# Steuerplatine_V2_0.net
KiCad netlist of a schematic drawn in EAGLE
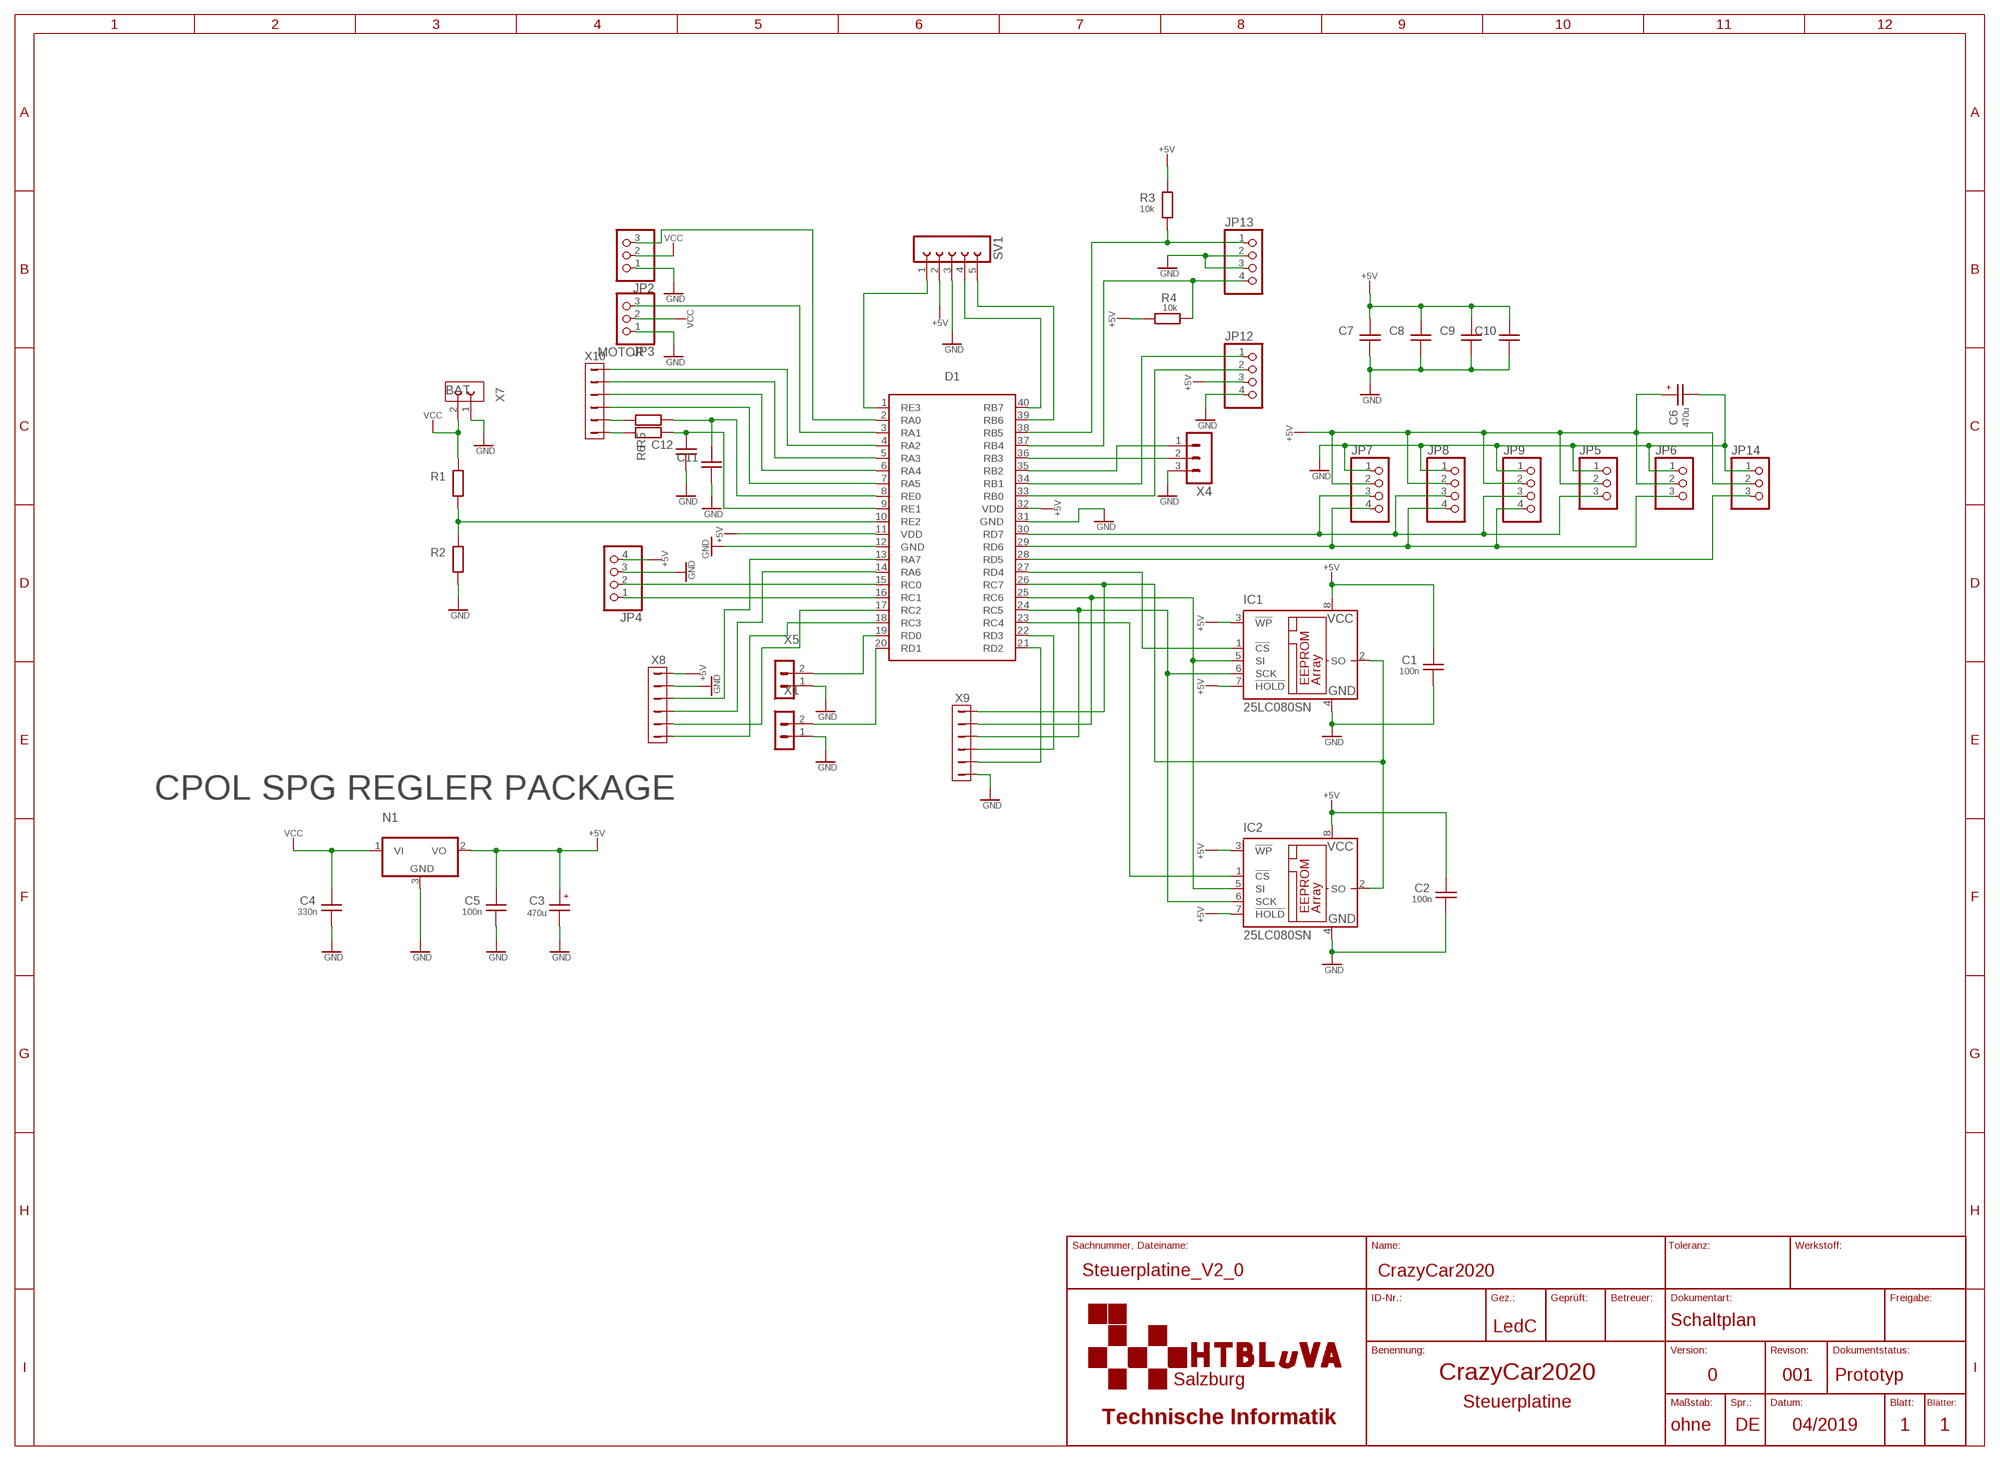
[diagram p0: schematic, sheet 1]

(export (version "E")
  (design (tool "Eeschema 10.0.6"))
  (components
    (comp (ref "C1")
      (value "100n")
      (footprint "eagle-import:C0603")
      (libsource (lib "eagle-import") (part "C-V_C0603"))
    )
    (comp (ref "C2")
      (value "100n")
      (footprint "eagle-import:C0603")
      (libsource (lib "eagle-import") (part "C-V_C0603"))
    )
    (comp (ref "C3")
      (value "470u")
      (footprint "eagle-import:E5-10,5")
      (libsource (lib "eagle-import") (part "C-POL-V_E5-10.5"))
    )
    (comp (ref "C4")
      (value "330n")
      (footprint "eagle-import:C1206")
      (libsource (lib "eagle-import") (part "C-V_C1206"))
    )
    (comp (ref "C5")
      (value "100n")
      (footprint "eagle-import:C1206")
      (libsource (lib "eagle-import") (part "C-V_C1206"))
    )
    (comp (ref "C6")
      (value "470u")
      (footprint "eagle-import:E5-10,5")
      (libsource (lib "eagle-import") (part "C-POL-V_E5-10.5"))
    )
    (comp (ref "C7")
      (value "C-V_C1206")
      (footprint "eagle-import:C1206")
      (libsource (lib "eagle-import") (part "C-V_C1206"))
    )
    (comp (ref "C8")
      (value "C-V_C1206")
      (footprint "eagle-import:C1206")
      (libsource (lib "eagle-import") (part "C-V_C1206"))
    )
    (comp (ref "C9")
      (value "C-V_C1206")
      (footprint "eagle-import:C1206")
      (libsource (lib "eagle-import") (part "C-V_C1206"))
    )
    (comp (ref "C10")
      (value "C-V_C1206")
      (footprint "eagle-import:C1206")
      (libsource (lib "eagle-import") (part "C-V_C1206"))
    )
    (comp (ref "C11")
      (value "C-V_C1206")
      (footprint "eagle-import:C1206")
      (libsource (lib "eagle-import") (part "C-V_C1206"))
    )
    (comp (ref "C12")
      (value "C-V_C1206")
      (footprint "eagle-import:C1206")
      (libsource (lib "eagle-import") (part "C-V_C1206"))
    )
    (comp (ref "D1")
      (value "EVAL_BRD_PIC18F46K421")
      (footprint "eagle-import:EVAL_BRD_PIC18F46K42")
      (libsource (lib "eagle-import") (part "EVAL_BRD_PIC18F46K421"))
    )
    (comp (ref "IC1")
      (value "25LC080SN")
      (footprint "eagle-import:SO-08")
      (fields (field (name "MF") "MICROCHIP") (field (name "MPN") "25LC080/SN"))
      (libsource (lib "eagle-import") (part "25SNLC080"))
    )
    (comp (ref "IC2")
      (value "25LC080SN")
      (footprint "eagle-import:SO-08")
      (fields (field (name "MF") "MICROCHIP") (field (name "MPN") "25LC080/SN"))
      (libsource (lib "eagle-import") (part "25SNLC080"))
    )
    (comp (ref "JP2")
      (value "PINHD-1X3")
      (footprint "eagle-import:1X03")
      (libsource (lib "eagle-import") (part "PINHD-1X3"))
    )
    (comp (ref "JP3")
      (value "PINHD-1X3")
      (footprint "eagle-import:1X03")
      (libsource (lib "eagle-import") (part "PINHD-1X3"))
    )
    (comp (ref "JP4")
      (value "PINHD-1X4")
      (footprint "eagle-import:1X04")
      (libsource (lib "eagle-import") (part "PINHD-1X4"))
    )
    (comp (ref "JP5")
      (value "PINHD-1X3")
      (footprint "eagle-import:1X03")
      (libsource (lib "eagle-import") (part "PINHD-1X3"))
    )
    (comp (ref "JP6")
      (value "PINHD-1X3")
      (footprint "eagle-import:1X03")
      (libsource (lib "eagle-import") (part "PINHD-1X3"))
    )
    (comp (ref "JP7")
      (value "PINHD-1X4")
      (footprint "eagle-import:1X04")
      (libsource (lib "eagle-import") (part "PINHD-1X4"))
    )
    (comp (ref "JP8")
      (value "PINHD-1X4")
      (footprint "eagle-import:1X04")
      (libsource (lib "eagle-import") (part "PINHD-1X4"))
    )
    (comp (ref "JP9")
      (value "PINHD-1X4")
      (footprint "eagle-import:1X04")
      (libsource (lib "eagle-import") (part "PINHD-1X4"))
    )
    (comp (ref "JP12")
      (value "PINHD-1X4")
      (footprint "eagle-import:1X04")
      (libsource (lib "eagle-import") (part "PINHD-1X4"))
    )
    (comp (ref "JP13")
      (value "PINHD-1X4")
      (footprint "eagle-import:1X04")
      (libsource (lib "eagle-import") (part "PINHD-1X4"))
    )
    (comp (ref "JP14")
      (value "PINHD-1X3")
      (footprint "eagle-import:1X03")
      (libsource (lib "eagle-import") (part "PINHD-1X3"))
    )
    (comp (ref "N1")
      (value "7805DT")
      (footprint "eagle-import:TO252")
      (libsource (lib "eagle-import") (part "78DT05"))
    )
    (comp (ref "R1")
      (value "R-V_R1206")
      (footprint "eagle-import:R1206")
      (libsource (lib "eagle-import") (part "R-V_R1206"))
    )
    (comp (ref "R2")
      (value "R-V_R1206")
      (footprint "eagle-import:R1206")
      (libsource (lib "eagle-import") (part "R-V_R1206"))
    )
    (comp (ref "R3")
      (value "10k")
      (footprint "eagle-import:R1206")
      (libsource (lib "eagle-import") (part "R-V_R1206"))
    )
    (comp (ref "R4")
      (value "10k")
      (footprint "eagle-import:R1206")
      (libsource (lib "eagle-import") (part "R-V_R1206"))
    )
    (comp (ref "R5")
      (value "R-V_R1206")
      (footprint "eagle-import:R1206")
      (libsource (lib "eagle-import") (part "R-V_R1206"))
    )
    (comp (ref "R6")
      (value "R-V_R1206")
      (footprint "eagle-import:R1206")
      (libsource (lib "eagle-import") (part "R-V_R1206"))
    )
    (comp (ref "SV1")
      (value "FE05-1")
      (footprint "eagle-import:FE05-1")
      (libsource (lib "eagle-import") (part "FE05-1"))
    )
    (comp (ref "X1")
      (value "M02")
      (footprint "eagle-import:02P")
      (libsource (lib "eagle-import") (part "M02"))
    )
    (comp (ref "X4")
      (value "MA03-1")
      (footprint "eagle-import:MA03-1")
      (libsource (lib "eagle-import") (part "MA03-1"))
    )
    (comp (ref "X5")
      (value "M02")
      (footprint "eagle-import:02P")
      (libsource (lib "eagle-import") (part "M02"))
    )
    (comp (ref "X7")
      (value "PRINTKLEMME2_PHOENIX_MPT")
      (footprint "eagle-import:PHOENIX_MPT")
      (libsource (lib "eagle-import") (part "PRINTKLEMME2_PHOENIX_MPT"))
    )
    (comp (ref "X8")
      (value "MA06-1_")
      (footprint "eagle-import:MA06-1")
      (libsource (lib "eagle-import") (part "MA06-1_"))
    )
    (comp (ref "X9")
      (value "MA06-1_")
      (footprint "eagle-import:MA06-1")
      (libsource (lib "eagle-import") (part "MA06-1_"))
    )
    (comp (ref "X10")
      (value "MA06-1_")
      (footprint "eagle-import:MA06-1")
      (libsource (lib "eagle-import") (part "MA06-1_"))
    )
  )
  (nets
    (net (code "1") (name "+5V") (class "Default")
      (node (ref "C1") (pin "1") (pinfunction "1_1") (pintype "passive"))
      (node (ref "C10") (pin "1") (pinfunction "1_1") (pintype "passive"))
      (node (ref "C2") (pin "1") (pinfunction "1_1") (pintype "passive"))
      (node (ref "C3") (pin "+") (pinfunction "+_+") (pintype "passive"))
      (node (ref "C5") (pin "1") (pinfunction "1_1") (pintype "passive"))
      (node (ref "C6") (pin "+") (pinfunction "+_+") (pintype "passive"))
      (node (ref "C7") (pin "1") (pinfunction "1_1") (pintype "passive"))
      (node (ref "C8") (pin "1") (pinfunction "1_1") (pintype "passive"))
      (node (ref "C9") (pin "1") (pinfunction "1_1") (pintype "passive"))
      (node (ref "D1") (pin "11") (pinfunction "VDD_11") (pintype "bidirectional"))
      (node (ref "D1") (pin "32") (pinfunction "VDD_32") (pintype "bidirectional"))
      (node (ref "IC1") (pin "3") (pinfunction "~{WP}_3") (pintype "input"))
      (node (ref "IC1") (pin "7") (pinfunction "~{HOLD}_7") (pintype "input"))
      (node (ref "IC1") (pin "8") (pinfunction "VCC_8") (pintype "power_in"))
      (node (ref "IC2") (pin "3") (pinfunction "~{WP}_3") (pintype "input"))
      (node (ref "IC2") (pin "7") (pinfunction "~{HOLD}_7") (pintype "input"))
      (node (ref "IC2") (pin "8") (pinfunction "VCC_8") (pintype "power_in"))
      (node (ref "JP12") (pin "3") (pinfunction "3_3") (pintype "passive"))
      (node (ref "JP14") (pin "2") (pinfunction "2_2") (pintype "passive"))
      (node (ref "JP4") (pin "4") (pinfunction "4_4") (pintype "passive"))
      (node (ref "JP5") (pin "2") (pinfunction "2_2") (pintype "passive"))
      (node (ref "JP6") (pin "2") (pinfunction "2_2") (pintype "passive"))
      (node (ref "JP7") (pin "2") (pinfunction "2_2") (pintype "passive"))
      (node (ref "JP8") (pin "2") (pinfunction "2_2") (pintype "passive"))
      (node (ref "JP9") (pin "2") (pinfunction "2_2") (pintype "passive"))
      (node (ref "N1") (pin "2") (pinfunction "VO_2") (pintype "passive"))
      (node (ref "R3") (pin "2") (pinfunction "2_2") (pintype "passive"))
      (node (ref "R4") (pin "1") (pinfunction "1_1") (pintype "passive"))
      (node (ref "SV1") (pin "2") (pinfunction "2_2") (pintype "passive"))
      (node (ref "X8") (pin "6") (pinfunction "6_6") (pintype "passive"))
    )
    (net (code "2") (name "GND") (class "Default")
      (node (ref "C1") (pin "2") (pinfunction "2_2") (pintype "passive"))
      (node (ref "C10") (pin "2") (pinfunction "2_2") (pintype "passive"))
      (node (ref "C11") (pin "2") (pinfunction "2_2") (pintype "passive"))
      (node (ref "C12") (pin "2") (pinfunction "2_2") (pintype "passive"))
      (node (ref "C2") (pin "2") (pinfunction "2_2") (pintype "passive"))
      (node (ref "C3") (pin "-") (pinfunction "-_-") (pintype "passive"))
      (node (ref "C4") (pin "2") (pinfunction "2_2") (pintype "passive"))
      (node (ref "C5") (pin "2") (pinfunction "2_2") (pintype "passive"))
      (node (ref "C6") (pin "-") (pinfunction "-_-") (pintype "passive"))
      (node (ref "C7") (pin "2") (pinfunction "2_2") (pintype "passive"))
      (node (ref "C8") (pin "2") (pinfunction "2_2") (pintype "passive"))
      (node (ref "C9") (pin "2") (pinfunction "2_2") (pintype "passive"))
      (node (ref "D1") (pin "12") (pinfunction "GND_12") (pintype "bidirectional"))
      (node (ref "D1") (pin "31") (pinfunction "GND_31") (pintype "bidirectional"))
      (node (ref "IC1") (pin "4") (pinfunction "GND_4") (pintype "power_in"))
      (node (ref "IC2") (pin "4") (pinfunction "GND_4") (pintype "power_in"))
      (node (ref "JP12") (pin "4") (pinfunction "4_4") (pintype "passive"))
      (node (ref "JP13") (pin "2") (pinfunction "2_2") (pintype "passive"))
      (node (ref "JP13") (pin "3") (pinfunction "3_3") (pintype "passive"))
      (node (ref "JP14") (pin "1") (pinfunction "1_1") (pintype "passive"))
      (node (ref "JP2") (pin "1") (pinfunction "1_1") (pintype "passive"))
      (node (ref "JP3") (pin "1") (pinfunction "1_1") (pintype "passive"))
      (node (ref "JP4") (pin "3") (pinfunction "3_3") (pintype "passive"))
      (node (ref "JP5") (pin "1") (pinfunction "1_1") (pintype "passive"))
      (node (ref "JP6") (pin "1") (pinfunction "1_1") (pintype "passive"))
      (node (ref "JP7") (pin "1") (pinfunction "1_1") (pintype "passive"))
      (node (ref "JP8") (pin "1") (pinfunction "1_1") (pintype "passive"))
      (node (ref "JP9") (pin "1") (pinfunction "1_1") (pintype "passive"))
      (node (ref "N1") (pin "3") (pinfunction "GND_3") (pintype "passive"))
      (node (ref "R2") (pin "1") (pinfunction "1_1") (pintype "passive"))
      (node (ref "SV1") (pin "3") (pinfunction "3_3") (pintype "passive"))
      (node (ref "X1") (pin "1") (pinfunction "1_1") (pintype "passive"))
      (node (ref "X4") (pin "3") (pinfunction "3_3") (pintype "passive"))
      (node (ref "X5") (pin "1") (pinfunction "1_1") (pintype "passive"))
      (node (ref "X7") (pin "1") (pinfunction "1_1") (pintype "passive"))
      (node (ref "X8") (pin "5") (pinfunction "5_5") (pintype "passive"))
      (node (ref "X9") (pin "1") (pinfunction "1_1") (pintype "passive"))
    )
    (net (code "3") (name "Net-(D1-RA0)") (class "Default")
      (node (ref "D1") (pin "2") (pinfunction "RA0_2") (pintype "bidirectional"))
      (node (ref "JP2") (pin "3") (pinfunction "3_3") (pintype "passive"))
    )
    (net (code "4") (name "Net-(D1-RA1)") (class "Default")
      (node (ref "D1") (pin "3") (pinfunction "RA1_3") (pintype "bidirectional"))
      (node (ref "JP3") (pin "3") (pinfunction "3_3") (pintype "passive"))
    )
    (net (code "5") (name "Net-(D1-RA2)") (class "Default")
      (node (ref "D1") (pin "4") (pinfunction "RA2_4") (pintype "bidirectional"))
      (node (ref "X10") (pin "6") (pinfunction "6_6") (pintype "passive"))
    )
    (net (code "6") (name "Net-(D1-RA3)") (class "Default")
      (node (ref "D1") (pin "5") (pinfunction "RA3_5") (pintype "bidirectional"))
      (node (ref "X10") (pin "5") (pinfunction "5_5") (pintype "passive"))
    )
    (net (code "7") (name "Net-(D1-RA4)") (class "Default")
      (node (ref "D1") (pin "6") (pinfunction "RA4_6") (pintype "bidirectional"))
      (node (ref "X10") (pin "4") (pinfunction "4_4") (pintype "passive"))
    )
    (net (code "8") (name "Net-(D1-RA5)") (class "Default")
      (node (ref "D1") (pin "7") (pinfunction "RA5_7") (pintype "bidirectional"))
      (node (ref "X10") (pin "3") (pinfunction "3_3") (pintype "passive"))
    )
    (net (code "9") (name "Net-(D1-RA6)") (class "Default")
      (node (ref "D1") (pin "14") (pinfunction "RA6_14") (pintype "bidirectional"))
      (node (ref "X8") (pin "3") (pinfunction "3_3") (pintype "passive"))
    )
    (net (code "10") (name "Net-(D1-RA7)") (class "Default")
      (node (ref "D1") (pin "13") (pinfunction "RA7_13") (pintype "bidirectional"))
      (node (ref "X8") (pin "4") (pinfunction "4_4") (pintype "passive"))
    )
    (net (code "11") (name "Net-(D1-RB0)") (class "Default")
      (node (ref "D1") (pin "33") (pinfunction "RB0_33") (pintype "bidirectional"))
      (node (ref "JP12") (pin "2") (pinfunction "2_2") (pintype "passive"))
    )
    (net (code "12") (name "Net-(D1-RB1)") (class "Default")
      (node (ref "D1") (pin "34") (pinfunction "RB1_34") (pintype "bidirectional"))
      (node (ref "JP12") (pin "1") (pinfunction "1_1") (pintype "passive"))
    )
    (net (code "13") (name "Net-(D1-RB2)") (class "Default")
      (node (ref "D1") (pin "35") (pinfunction "RB2_35") (pintype "bidirectional"))
      (node (ref "X4") (pin "1") (pinfunction "1_1") (pintype "passive"))
    )
    (net (code "14") (name "Net-(D1-RB3)") (class "Default")
      (node (ref "D1") (pin "36") (pinfunction "RB3_36") (pintype "bidirectional"))
      (node (ref "X4") (pin "2") (pinfunction "2_2") (pintype "passive"))
    )
    (net (code "15") (name "Net-(D1-RB4)") (class "Default")
      (node (ref "D1") (pin "37") (pinfunction "RB4_37") (pintype "bidirectional"))
      (node (ref "JP13") (pin "4") (pinfunction "4_4") (pintype "passive"))
      (node (ref "R4") (pin "2") (pinfunction "2_2") (pintype "passive"))
    )
    (net (code "16") (name "Net-(D1-RB5)") (class "Default")
      (node (ref "D1") (pin "38") (pinfunction "RB5_38") (pintype "bidirectional"))
      (node (ref "JP13") (pin "1") (pinfunction "1_1") (pintype "passive"))
      (node (ref "R3") (pin "1") (pinfunction "1_1") (pintype "passive"))
    )
    (net (code "17") (name "Net-(D1-RB6)") (class "Default")
      (node (ref "D1") (pin "39") (pinfunction "RB6_39") (pintype "bidirectional"))
      (node (ref "SV1") (pin "5") (pinfunction "5_5") (pintype "passive"))
    )
    (net (code "18") (name "Net-(D1-RB7)") (class "Default")
      (node (ref "D1") (pin "40") (pinfunction "RB7_40") (pintype "bidirectional"))
      (node (ref "SV1") (pin "4") (pinfunction "4_4") (pintype "passive"))
    )
    (net (code "19") (name "Net-(D1-RC0)") (class "Default")
      (node (ref "D1") (pin "15") (pinfunction "RC0_15") (pintype "bidirectional"))
      (node (ref "JP4") (pin "2") (pinfunction "2_2") (pintype "passive"))
    )
    (net (code "20") (name "Net-(D1-RC1)") (class "Default")
      (node (ref "D1") (pin "16") (pinfunction "RC1_16") (pintype "bidirectional"))
      (node (ref "JP4") (pin "1") (pinfunction "1_1") (pintype "passive"))
    )
    (net (code "21") (name "Net-(D1-RC2)") (class "Default")
      (node (ref "D1") (pin "17") (pinfunction "RC2_17") (pintype "bidirectional"))
      (node (ref "X8") (pin "2") (pinfunction "2_2") (pintype "passive"))
    )
    (net (code "22") (name "Net-(D1-RC3)") (class "Default")
      (node (ref "D1") (pin "18") (pinfunction "RC3_18") (pintype "bidirectional"))
      (node (ref "X8") (pin "1") (pinfunction "1_1") (pintype "passive"))
    )
    (net (code "23") (name "Net-(D1-RC4)") (class "Default")
      (node (ref "D1") (pin "23") (pinfunction "RC4_23") (pintype "bidirectional"))
      (node (ref "IC2") (pin "1") (pinfunction "~{CS}_1") (pintype "input"))
    )
    (net (code "24") (name "Net-(D1-RC5)") (class "Default")
      (node (ref "D1") (pin "24") (pinfunction "RC5_24") (pintype "bidirectional"))
      (node (ref "IC1") (pin "6") (pinfunction "SCK_6") (pintype "input"))
      (node (ref "IC2") (pin "6") (pinfunction "SCK_6") (pintype "input"))
      (node (ref "X9") (pin "4") (pinfunction "4_4") (pintype "passive"))
    )
    (net (code "25") (name "Net-(D1-RC6)") (class "Default")
      (node (ref "D1") (pin "25") (pinfunction "RC6_25") (pintype "bidirectional"))
      (node (ref "IC1") (pin "5") (pinfunction "SI_5") (pintype "input"))
      (node (ref "IC2") (pin "5") (pinfunction "SI_5") (pintype "input"))
      (node (ref "X9") (pin "5") (pinfunction "5_5") (pintype "passive"))
    )
    (net (code "26") (name "Net-(D1-RC7)") (class "Default")
      (node (ref "D1") (pin "26") (pinfunction "RC7_26") (pintype "bidirectional"))
      (node (ref "IC1") (pin "2") (pinfunction "SO_2") (pintype "bidirectional"))
      (node (ref "IC2") (pin "2") (pinfunction "SO_2") (pintype "bidirectional"))
      (node (ref "X9") (pin "6") (pinfunction "6_6") (pintype "passive"))
    )
    (net (code "27") (name "Net-(D1-RD0)") (class "Default")
      (node (ref "D1") (pin "19") (pinfunction "RD0_19") (pintype "bidirectional"))
      (node (ref "X5") (pin "2") (pinfunction "2_2") (pintype "passive"))
    )
    (net (code "28") (name "Net-(D1-RD1)") (class "Default")
      (node (ref "D1") (pin "20") (pinfunction "RD1_20") (pintype "bidirectional"))
      (node (ref "X1") (pin "2") (pinfunction "2_2") (pintype "passive"))
    )
    (net (code "29") (name "Net-(D1-RD2)") (class "Default")
      (node (ref "D1") (pin "21") (pinfunction "RD2_21") (pintype "bidirectional"))
      (node (ref "X9") (pin "2") (pinfunction "2_2") (pintype "passive"))
    )
    (net (code "30") (name "Net-(D1-RD3)") (class "Default")
      (node (ref "D1") (pin "22") (pinfunction "RD3_22") (pintype "bidirectional"))
      (node (ref "X9") (pin "3") (pinfunction "3_3") (pintype "passive"))
    )
    (net (code "31") (name "Net-(D1-RD4)") (class "Default")
      (node (ref "D1") (pin "27") (pinfunction "RD4_27") (pintype "bidirectional"))
      (node (ref "IC1") (pin "1") (pinfunction "~{CS}_1") (pintype "input"))
    )
    (net (code "32") (name "Net-(D1-RD5)") (class "Default")
      (node (ref "D1") (pin "28") (pinfunction "RD5_28") (pintype "bidirectional"))
      (node (ref "JP14") (pin "3") (pinfunction "3_3") (pintype "passive"))
    )
    (net (code "33") (name "Net-(D1-RD6)") (class "Default")
      (node (ref "D1") (pin "29") (pinfunction "RD6_29") (pintype "bidirectional"))
      (node (ref "JP6") (pin "3") (pinfunction "3_3") (pintype "passive"))
      (node (ref "JP7") (pin "4") (pinfunction "4_4") (pintype "passive"))
      (node (ref "JP8") (pin "4") (pinfunction "4_4") (pintype "passive"))
      (node (ref "JP9") (pin "4") (pinfunction "4_4") (pintype "passive"))
    )
    (net (code "34") (name "Net-(D1-RD7)") (class "Default")
      (node (ref "D1") (pin "30") (pinfunction "RD7_30") (pintype "bidirectional"))
      (node (ref "JP5") (pin "3") (pinfunction "3_3") (pintype "passive"))
      (node (ref "JP7") (pin "3") (pinfunction "3_3") (pintype "passive"))
      (node (ref "JP8") (pin "3") (pinfunction "3_3") (pintype "passive"))
      (node (ref "JP9") (pin "3") (pinfunction "3_3") (pintype "passive"))
    )
    (net (code "35") (name "Net-(D1-RE0)") (class "Default")
      (node (ref "C11") (pin "1") (pinfunction "1_1") (pintype "passive"))
      (node (ref "D1") (pin "8") (pinfunction "RE0_8") (pintype "bidirectional"))
      (node (ref "R5") (pin "1") (pinfunction "1_1") (pintype "passive"))
    )
    (net (code "36") (name "Net-(D1-RE1)") (class "Default")
      (node (ref "C12") (pin "1") (pinfunction "1_1") (pintype "passive"))
      (node (ref "D1") (pin "9") (pinfunction "RE1_9") (pintype "bidirectional"))
      (node (ref "R6") (pin "1") (pinfunction "1_1") (pintype "passive"))
    )
    (net (code "37") (name "Net-(D1-RE2)") (class "Default")
      (node (ref "D1") (pin "10") (pinfunction "RE2_10") (pintype "bidirectional"))
      (node (ref "R1") (pin "1") (pinfunction "1_1") (pintype "passive"))
      (node (ref "R2") (pin "2") (pinfunction "2_2") (pintype "passive"))
    )
    (net (code "38") (name "Net-(D1-RE3)") (class "Default")
      (node (ref "D1") (pin "1") (pinfunction "RE3_1") (pintype "bidirectional"))
      (node (ref "SV1") (pin "1") (pinfunction "1_1") (pintype "passive"))
    )
    (net (code "39") (name "Net-(R5-Pad2)") (class "Default")
      (node (ref "R5") (pin "2") (pinfunction "2_2") (pintype "passive"))
      (node (ref "X10") (pin "2") (pinfunction "2_2") (pintype "passive"))
    )
    (net (code "40") (name "Net-(R6-Pad2)") (class "Default")
      (node (ref "R6") (pin "2") (pinfunction "2_2") (pintype "passive"))
      (node (ref "X10") (pin "1") (pinfunction "1_1") (pintype "passive"))
    )
    (net (code "41") (name "VCC") (class "Default")
      (node (ref "C4") (pin "1") (pinfunction "1_1") (pintype "passive"))
      (node (ref "JP2") (pin "2") (pinfunction "2_2") (pintype "passive"))
      (node (ref "JP3") (pin "2") (pinfunction "2_2") (pintype "passive"))
      (node (ref "N1") (pin "1") (pinfunction "VI_1") (pintype "input"))
      (node (ref "R1") (pin "2") (pinfunction "2_2") (pintype "passive"))
      (node (ref "X7") (pin "2") (pinfunction "2_2") (pintype "passive"))
    )
  )
)
